# HW_Mechanical_Parts.net
KiCad netlist of a schematic drawn in Altium Designer
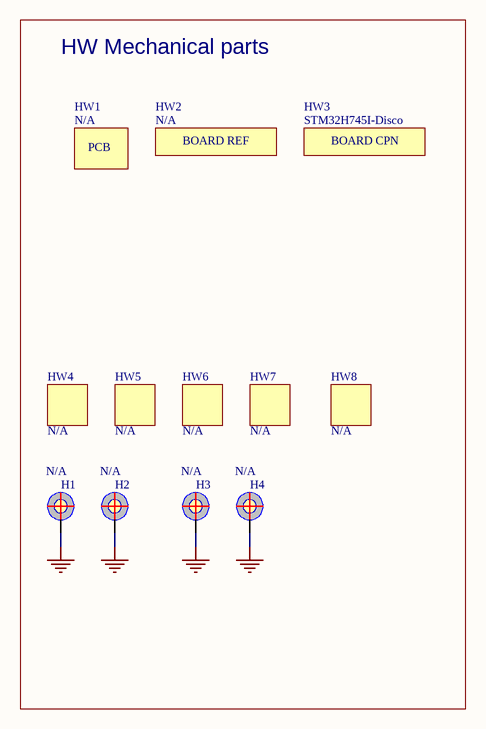
[diagram p0: HW_Mechanical_Parts.SchDoc]

(export (version "E")
  (design (tool "Eeschema 10.0.6"))
  (components
    (comp (ref "H1")
      (value "N/A")
      (footprint "PTH_350_700")
      (description "POSITION HOLE C7D3R5")
      (fields (field (name "INTERNAL_PART_NUMBER") "MCD-00328"))
      (libsource (lib "MCD_PARTS_database") (part "POSITION HOLE C7D3R5"))
    )
    (comp (ref "H2")
      (value "N/A")
      (footprint "PTH_350_700")
      (description "POSITION HOLE C7D3R5")
      (fields (field (name "INTERNAL_PART_NUMBER") "MCD-00328"))
      (libsource (lib "MCD_PARTS_database") (part "POSITION HOLE C7D3R5"))
    )
    (comp (ref "H3")
      (value "N/A")
      (footprint "PTH_350_700")
      (description "POSITION HOLE C7D3R5")
      (fields (field (name "INTERNAL_PART_NUMBER") "MCD-00328"))
      (libsource (lib "MCD_PARTS_database") (part "POSITION HOLE C7D3R5"))
    )
    (comp (ref "H4")
      (value "N/A")
      (footprint "PTH_350_700")
      (description "POSITION HOLE C7D3R5")
      (fields (field (name "INTERNAL_PART_NUMBER") "MCD-00328"))
      (libsource (lib "MCD_PARTS_database") (part "POSITION HOLE C7D3R5"))
    )
    (comp (ref "HW1")
      (value "N/A")
      (description "PCB, xxxx for PCB ref, Y for revision")
      (fields
        (field (name "INTERNAL_PART_NUMBER") "MCD-00036")
        (field (name "MANUFACTURER_PART_NUMBER") "n/a")
        (field (name "PROVIDED_BY") "Subcon")
      )
      (libsource (lib "MCD_PARTS_database") (part "PCB"))
    )
    (comp (ref "HW2")
      (value "N/A")
      (description "Sticker to mention board reference + serial number")
      (fields
        (field (name "INTERNAL_PART_NUMBER") "MCD-00235")
        (field (name "Comment") "STICKER_BOARD_REF")
        (field (name "PROVIDED_BY") "Subcon")
      )
      (libsource (lib "MCD_PARTS_database") (part "STICKER_BOARD_REF"))
    )
    (comp (ref "HW3")
      (value "STM32H745I-Disco")
      (description "Sticker to mention board CPN code")
      (fields
        (field (name "INTERNAL_PART_NUMBER") "MCD-00549")
        (field (name "Comment") "STICKER_BOARD_CPN")
        (field (name "PROVIDED_BY") "Subcon")
      )
      (libsource (lib "MCD_PARTS_database") (part "STICKER_BOARD_CPN"))
    )
    (comp (ref "HW4")
      (value "N/A")
      (footprint "LOGO_STM_BIG")
      (description "\"STMicroelectronics\" logo footprint for PCB")
      (fields
        (field (name "INTERNAL_PART_NUMBER") "MCD-00625")
        (field (name "MANUFACTURER_PART_NUMBER") "n/a")
      )
      (libsource (lib "MCD_PARTS_database") (part "Logo"))
    )
    (comp (ref "HW5")
      (value "N/A")
      (footprint "LOGO_CE")
      (description "\"CE\" logo footprint for PCB")
      (fields (field (name "INTERNAL_PART_NUMBER") "MCD-00626") (field (name "Comment") "Logo"))
      (libsource (lib "MCD_PARTS_database") (part "Logo"))
    )
    (comp (ref "HW6")
      (value "N/A")
      (footprint "LOGO_MAIN_1")
      (description "\"Hand\" ESD logo footprint for PCB")
      (fields
        (field (name "INTERNAL_PART_NUMBER") "MCD-00627")
        (field (name "MANUFACTURER_PART_NUMBER") "n/a")
      )
      (libsource (lib "MCD_PARTS_database") (part "Logo"))
    )
    (comp (ref "HW7")
      (value "N/A")
      (footprint "LOGO_ROHS")
      (description "\"ROHS\" logo footprint for PCB")
      (fields (field (name "INTERNAL_PART_NUMBER") "MCD-00628") (field (name "Comment") "Logo"))
      (libsource (lib "MCD_PARTS_database") (part "Logo"))
    )
    (comp (ref "HW8")
      (value "N/A")
      (footprint "LOGO_STM32")
      (description "STM32 logo footprint for PCB")
      (fields (field (name "INTERNAL_PART_NUMBER") "MCD-00629") (field (name "Comment") "Logo"))
      (libsource (lib "MCD_PARTS_database") (part "Logo"))
    )
  )
  (nets
    (net (code "1") (name "GND") (class "Default")
      (node (ref "H1") (pin "1") (pinfunction "1_1") (pintype "passive"))
      (node (ref "H2") (pin "1") (pinfunction "1_1") (pintype "passive"))
      (node (ref "H3") (pin "1") (pinfunction "1_1") (pintype "passive"))
      (node (ref "H4") (pin "1") (pinfunction "1_1") (pintype "passive"))
    )
  )
)
